# sla2216-conn-coax.net
KiCad netlist of a schematic drawn in Altium Designer
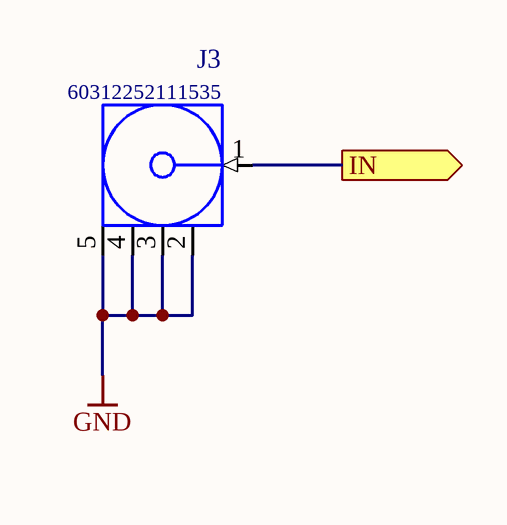
[diagram p0: sla2216-conn-coax.SchDoc]

(export (version "E")
  (design (tool "Eeschema 10.0.6"))
  (components
    (comp (ref "J3")
      (value "60312252111535")
      (footprint "60312252111535")
      (description "WR-SMA Connector, PCB End Launch Jack, IP67, DC~6GHz, 50Ohm")
      (fields (field (name "MANUFACTURER") "Wurth Elektronik"))
      (libsource (lib "Altium_WR-SMA (rev21c)") (part "60312252111535"))
    )
  )
  (nets
    (net (code "1") (name "/IN") (class "Default")
      (node (ref "J3") (pin "1") (pinfunction "Signal_1") (pintype "input"))
    )
    (net (code "2") (name "GND") (class "Default")
      (node (ref "J3") (pin "2") (pinfunction "GND_2") (pintype "power_in"))
      (node (ref "J3") (pin "3") (pinfunction "GND_3") (pintype "power_in"))
      (node (ref "J3") (pin "4") (pinfunction "GND_4") (pintype "power_in"))
      (node (ref "J3") (pin "5") (pinfunction "GND_5") (pintype "power_in"))
    )
  )
)
